# main_plate.net
KiCad netlist of a schematic drawn in EAGLE
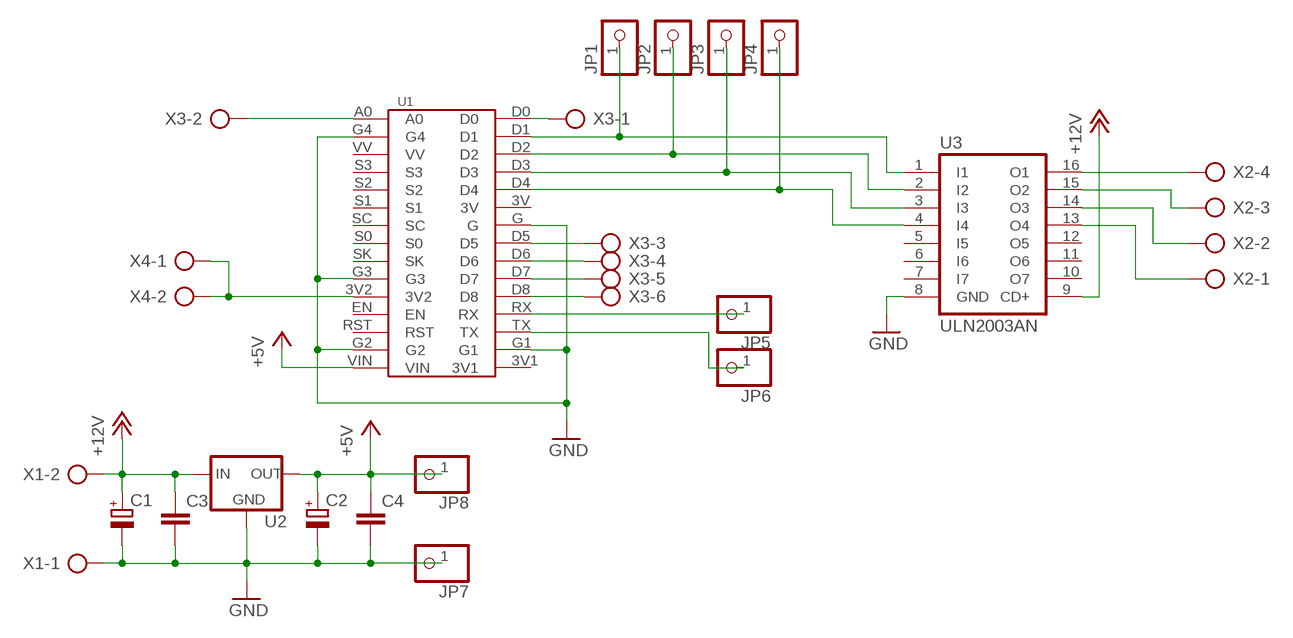
[diagram p0: schematic, sheet 1]

(export (version "E")
  (design (tool "Eeschema 10.0.6"))
  (components
    (comp (ref "C1")
      (value "CPOL-EUE3.5-8")
      (footprint "eagle-import:E3,5-8")
      (libsource (lib "eagle-import") (part "CPOL-EUE3.5-8"))
    )
    (comp (ref "C2")
      (value "CPOL-EUE3.5-8")
      (footprint "eagle-import:E3,5-8")
      (libsource (lib "eagle-import") (part "CPOL-EUE3.5-8"))
    )
    (comp (ref "C3")
      (value "C-EU025-025X050")
      (footprint "eagle-import:C025-025X050")
      (libsource (lib "eagle-import") (part "C-EU025-025X050"))
    )
    (comp (ref "C4")
      (value "C-EU025-025X050")
      (footprint "eagle-import:C025-025X050")
      (libsource (lib "eagle-import") (part "C-EU025-025X050"))
    )
    (comp (ref "JP1")
      (value "PINHD-1X1")
      (footprint "eagle-import:1X01")
      (libsource (lib "eagle-import") (part "PINHD-1X1"))
    )
    (comp (ref "JP2")
      (value "PINHD-1X1")
      (footprint "eagle-import:1X01")
      (libsource (lib "eagle-import") (part "PINHD-1X1"))
    )
    (comp (ref "JP3")
      (value "PINHD-1X1")
      (footprint "eagle-import:1X01")
      (libsource (lib "eagle-import") (part "PINHD-1X1"))
    )
    (comp (ref "JP4")
      (value "PINHD-1X1")
      (footprint "eagle-import:1X01")
      (libsource (lib "eagle-import") (part "PINHD-1X1"))
    )
    (comp (ref "JP5")
      (value "PINHD-1X1")
      (footprint "eagle-import:1X01")
      (libsource (lib "eagle-import") (part "PINHD-1X1"))
    )
    (comp (ref "JP6")
      (value "PINHD-1X1")
      (footprint "eagle-import:1X01")
      (libsource (lib "eagle-import") (part "PINHD-1X1"))
    )
    (comp (ref "JP7")
      (value "PINHD-1X1")
      (footprint "eagle-import:1X01")
      (libsource (lib "eagle-import") (part "PINHD-1X1"))
    )
    (comp (ref "JP8")
      (value "PINHD-1X1")
      (footprint "eagle-import:1X01")
      (libsource (lib "eagle-import") (part "PINHD-1X1"))
    )
    (comp (ref "U1")
      (value "LOLIN")
      (footprint "eagle-import:LOLIN")
      (libsource (lib "eagle-import") (part "LOLIN"))
    )
    (comp (ref "U2")
      (value "78XXS")
      (footprint "eagle-import:78XXS")
      (libsource (lib "eagle-import") (part "78XXS"))
    )
    (comp (ref "U3")
      (value "ULN2003AN")
      (footprint "eagle-import:DIL16")
      (libsource (lib "eagle-import") (part "ULN2003AN"))
    )
    (comp (ref "X1")
      (value "AK300/2")
      (footprint "eagle-import:AK300_2")
      (libsource (lib "eagle-import") (part "AK300/2"))
    )
    (comp (ref "X2")
      (value "AK300/4")
      (footprint "eagle-import:AK300_4")
      (libsource (lib "eagle-import") (part "AK300/4"))
    )
    (comp (ref "X3")
      (value "AK300/6")
      (footprint "eagle-import:AK300_6")
      (libsource (lib "eagle-import") (part "AK300/6"))
    )
    (comp (ref "X4")
      (value "AK300/2")
      (footprint "eagle-import:AK300_2")
      (libsource (lib "eagle-import") (part "AK300/2"))
    )
  )
  (nets
    (net (code "1") (name "+5V") (class "Default")
      (node (ref "C2") (pin "+") (pinfunction "+_+") (pintype "passive"))
      (node (ref "C4") (pin "1") (pinfunction "1_1") (pintype "passive"))
      (node (ref "JP8") (pin "1") (pinfunction "1_1") (pintype "passive"))
      (node (ref "U1") (pin "VIN") (pinfunction "VIN_VIN") (pintype "bidirectional"))
      (node (ref "U2") (pin "OUT") (pinfunction "OUT_OUT") (pintype "passive"))
    )
    (net (code "2") (name "+12V") (class "Default")
      (node (ref "C1") (pin "+") (pinfunction "+_+") (pintype "passive"))
      (node (ref "C3") (pin "1") (pinfunction "1_1") (pintype "passive"))
      (node (ref "U2") (pin "IN") (pinfunction "IN_IN") (pintype "input"))
      (node (ref "U3") (pin "9") (pinfunction "CD+_9") (pintype "passive"))
      (node (ref "X1") (pin "2") (pinfunction "KL_2") (pintype "passive"))
    )
    (net (code "3") (name "GND") (class "Default")
      (node (ref "C1") (pin "-") (pinfunction "-_-") (pintype "passive"))
      (node (ref "C2") (pin "-") (pinfunction "-_-") (pintype "passive"))
      (node (ref "C3") (pin "2") (pinfunction "2_2") (pintype "passive"))
      (node (ref "C4") (pin "2") (pinfunction "2_2") (pintype "passive"))
      (node (ref "JP7") (pin "1") (pinfunction "1_1") (pintype "passive"))
      (node (ref "U1") (pin "G") (pinfunction "G_G") (pintype "bidirectional"))
      (node (ref "U1") (pin "G1") (pinfunction "G1_G1") (pintype "bidirectional"))
      (node (ref "U1") (pin "G2") (pinfunction "G2_G2") (pintype "bidirectional"))
      (node (ref "U1") (pin "G3") (pinfunction "G3_G3") (pintype "bidirectional"))
      (node (ref "U1") (pin "G4") (pinfunction "G4_G4") (pintype "bidirectional"))
      (node (ref "U2") (pin "GND") (pinfunction "GND_GND") (pintype "input"))
      (node (ref "U3") (pin "8") (pinfunction "GND_8") (pintype "power_in"))
      (node (ref "X1") (pin "1") (pinfunction "KL_1") (pintype "passive"))
    )
    (net (code "4") (name "Net-(JP5-Pad1)") (class "Default")
      (node (ref "JP5") (pin "1") (pinfunction "1_1") (pintype "passive"))
      (node (ref "U1") (pin "RX") (pinfunction "RX_RX") (pintype "bidirectional"))
    )
    (net (code "5") (name "Net-(JP6-Pad1)") (class "Default")
      (node (ref "JP6") (pin "1") (pinfunction "1_1") (pintype "passive"))
      (node (ref "U1") (pin "TX") (pinfunction "TX_TX") (pintype "bidirectional"))
    )
    (net (code "6") (name "Net-(U3-I1)") (class "Default")
      (node (ref "JP1") (pin "1") (pinfunction "1_1") (pintype "passive"))
      (node (ref "U1") (pin "D1") (pinfunction "D1_D1") (pintype "bidirectional"))
      (node (ref "U3") (pin "1") (pinfunction "I1_1") (pintype "input"))
    )
    (net (code "7") (name "Net-(U3-I2)") (class "Default")
      (node (ref "JP2") (pin "1") (pinfunction "1_1") (pintype "passive"))
      (node (ref "U1") (pin "D2") (pinfunction "D2_D2") (pintype "bidirectional"))
      (node (ref "U3") (pin "2") (pinfunction "I2_2") (pintype "input"))
    )
    (net (code "8") (name "Net-(U3-I3)") (class "Default")
      (node (ref "JP3") (pin "1") (pinfunction "1_1") (pintype "passive"))
      (node (ref "U1") (pin "D3") (pinfunction "D3_D3") (pintype "bidirectional"))
      (node (ref "U3") (pin "3") (pinfunction "I3_3") (pintype "input"))
    )
    (net (code "9") (name "Net-(U3-I4)") (class "Default")
      (node (ref "JP4") (pin "1") (pinfunction "1_1") (pintype "passive"))
      (node (ref "U1") (pin "D4") (pinfunction "D4_D4") (pintype "bidirectional"))
      (node (ref "U3") (pin "4") (pinfunction "I4_4") (pintype "input"))
    )
    (net (code "10") (name "Net-(U3-O1)") (class "Default")
      (node (ref "U3") (pin "16") (pinfunction "O1_16") (pintype "open_collector"))
      (node (ref "X2") (pin "4") (pinfunction "KL_4") (pintype "passive"))
    )
    (net (code "11") (name "Net-(U3-O2)") (class "Default")
      (node (ref "U3") (pin "15") (pinfunction "O2_15") (pintype "open_collector"))
      (node (ref "X2") (pin "3") (pinfunction "KL_3") (pintype "passive"))
    )
    (net (code "12") (name "Net-(U3-O3)") (class "Default")
      (node (ref "U3") (pin "14") (pinfunction "O3_14") (pintype "open_collector"))
      (node (ref "X2") (pin "2") (pinfunction "KL_2") (pintype "passive"))
    )
    (net (code "13") (name "Net-(U3-O4)") (class "Default")
      (node (ref "U3") (pin "13") (pinfunction "O4_13") (pintype "open_collector"))
      (node (ref "X2") (pin "1") (pinfunction "KL_1") (pintype "passive"))
    )
    (net (code "14") (name "Net-(X3A-KL)") (class "Default")
      (node (ref "U1") (pin "D0") (pinfunction "D0_D0") (pintype "bidirectional"))
      (node (ref "X3") (pin "1") (pinfunction "KL_1") (pintype "passive"))
    )
    (net (code "15") (name "Net-(X3B-KL)") (class "Default")
      (node (ref "U1") (pin "A0") (pinfunction "A0_A0") (pintype "bidirectional"))
      (node (ref "X3") (pin "2") (pinfunction "KL_2") (pintype "passive"))
    )
    (net (code "16") (name "Net-(X3C-KL)") (class "Default")
      (node (ref "U1") (pin "D5") (pinfunction "D5_D5") (pintype "bidirectional"))
      (node (ref "X3") (pin "3") (pinfunction "KL_3") (pintype "passive"))
    )
    (net (code "17") (name "Net-(X3D-KL)") (class "Default")
      (node (ref "U1") (pin "D6") (pinfunction "D6_D6") (pintype "bidirectional"))
      (node (ref "X3") (pin "4") (pinfunction "KL_4") (pintype "passive"))
    )
    (net (code "18") (name "Net-(X3E-KL)") (class "Default")
      (node (ref "U1") (pin "D7") (pinfunction "D7_D7") (pintype "bidirectional"))
      (node (ref "X3") (pin "5") (pinfunction "KL_5") (pintype "passive"))
    )
    (net (code "19") (name "Net-(X3F-KL)") (class "Default")
      (node (ref "U1") (pin "D8") (pinfunction "D8_D8") (pintype "bidirectional"))
      (node (ref "X3") (pin "6") (pinfunction "KL_6") (pintype "passive"))
    )
    (net (code "20") (name "Net-(X4A-KL)") (class "Default")
      (node (ref "U1") (pin "3V2") (pinfunction "3V2_3V2") (pintype "bidirectional"))
      (node (ref "X4") (pin "1") (pinfunction "KL_1") (pintype "passive"))
      (node (ref "X4") (pin "2") (pinfunction "KL_2") (pintype "passive"))
    )
    (net (code "21") (name "unconnected-(U1-Pad3V)") (class "Default")
      (node (ref "U1") (pin "3V") (pinfunction "3V_3V") (pintype "bidirectional"))
    )
    (net (code "22") (name "unconnected-(U1-Pad3V1)") (class "Default")
      (node (ref "U1") (pin "3V1") (pinfunction "3V1_3V1") (pintype "bidirectional"))
    )
    (net (code "23") (name "unconnected-(U1-PadEN)") (class "Default")
      (node (ref "U1") (pin "EN") (pinfunction "EN_EN") (pintype "bidirectional"))
    )
    (net (code "24") (name "unconnected-(U1-PadRST)") (class "Default")
      (node (ref "U1") (pin "RST") (pinfunction "RST_RST") (pintype "bidirectional"))
    )
    (net (code "25") (name "unconnected-(U1-PadS0)") (class "Default")
      (node (ref "U1") (pin "S0") (pinfunction "S0_S0") (pintype "bidirectional"))
    )
    (net (code "26") (name "unconnected-(U1-PadS1)") (class "Default")
      (node (ref "U1") (pin "S1") (pinfunction "S1_S1") (pintype "bidirectional"))
    )
    (net (code "27") (name "unconnected-(U1-PadS2)") (class "Default")
      (node (ref "U1") (pin "S2") (pinfunction "S2_S2") (pintype "bidirectional"))
    )
    (net (code "28") (name "unconnected-(U1-PadS3)") (class "Default")
      (node (ref "U1") (pin "S3") (pinfunction "S3_S3") (pintype "bidirectional"))
    )
    (net (code "29") (name "unconnected-(U1-PadSC)") (class "Default")
      (node (ref "U1") (pin "SC") (pinfunction "SC_SC") (pintype "bidirectional"))
    )
    (net (code "30") (name "unconnected-(U1-PadSK)") (class "Default")
      (node (ref "U1") (pin "SK") (pinfunction "SK_SK") (pintype "bidirectional"))
    )
    (net (code "31") (name "unconnected-(U1-PadVV)") (class "Default")
      (node (ref "U1") (pin "VV") (pinfunction "VV_VV") (pintype "bidirectional"))
    )
    (net (code "32") (name "unconnected-(U3-I5-Pad5)") (class "Default")
      (node (ref "U3") (pin "5") (pinfunction "I5_5") (pintype "input"))
    )
    (net (code "33") (name "unconnected-(U3-I6-Pad6)") (class "Default")
      (node (ref "U3") (pin "6") (pinfunction "I6_6") (pintype "input"))
    )
    (net (code "34") (name "unconnected-(U3-I7-Pad7)") (class "Default")
      (node (ref "U3") (pin "7") (pinfunction "I7_7") (pintype "input"))
    )
    (net (code "35") (name "unconnected-(U3-O5-Pad12)") (class "Default")
      (node (ref "U3") (pin "12") (pinfunction "O5_12") (pintype "open_collector"))
    )
    (net (code "36") (name "unconnected-(U3-O6-Pad11)") (class "Default")
      (node (ref "U3") (pin "11") (pinfunction "O6_11") (pintype "open_collector"))
    )
    (net (code "37") (name "unconnected-(U3-O7-Pad10)") (class "Default")
      (node (ref "U3") (pin "10") (pinfunction "O7_10") (pintype "open_collector"))
    )
  )
)
